# 02_Power.net
KiCad netlist of a schematic drawn in Altium Designer
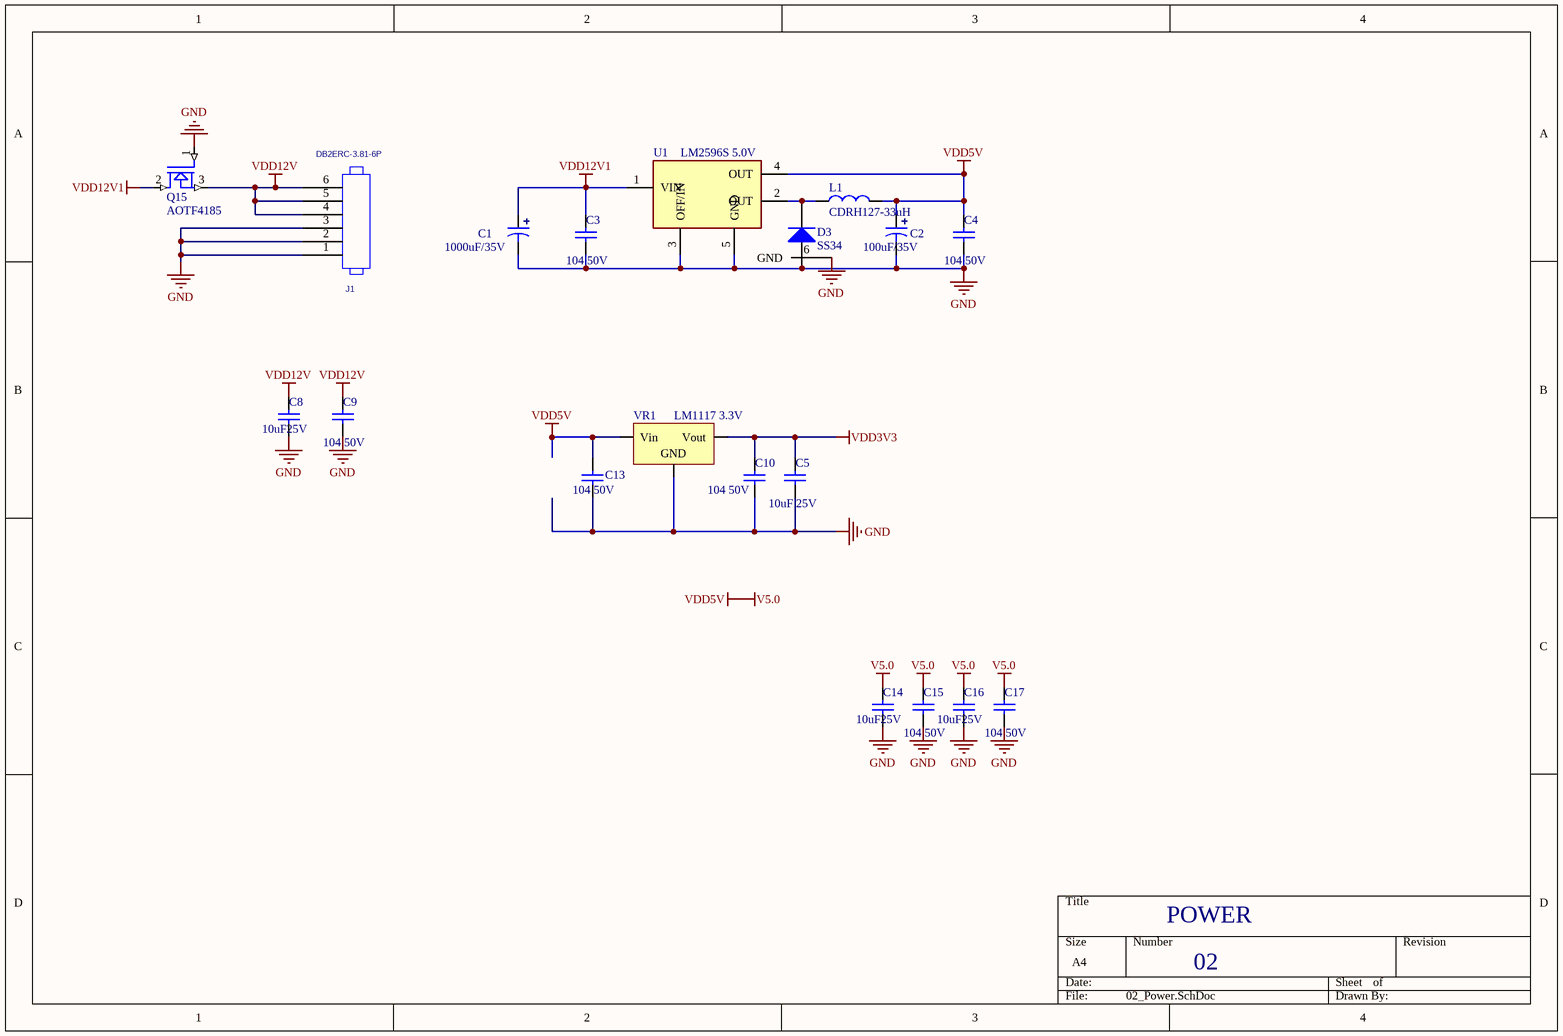
[diagram p0: 02_Power.SchDoc]

(export (version "E")
  (design (tool "Eeschema 10.0.6"))
  (components
    (comp (ref "C1")
      (value "1000uF/35V")
      (footprint "10*16")
      (description "电解电容")
      (libsource (lib "XiaoyI") (part "CAP2"))
    )
    (comp (ref "C2")
      (value "100uF/35V")
      (footprint "6*8")
      (description "电解电容")
      (libsource (lib "XiaoyI") (part "CAP2"))
    )
    (comp (ref "C3")
      (value "104 50V")
      (footprint "SMD-0805C")
      (description "贴片电容 10%")
      (libsource (lib "XiaoyI") (part "CAP4"))
    )
    (comp (ref "C4")
      (value "104 50V")
      (footprint "SMD-0805C")
      (description "贴片电容 10%")
      (libsource (lib "XiaoyI") (part "CAP4"))
    )
    (comp (ref "C5")
      (value "10uF 25V")
      (footprint "SMD-0603C")
      (description "贴片电容 20%")
      (libsource (lib "XiaoyI") (part "CAP4"))
    )
    (comp (ref "C8")
      (value "10uF25V")
      (footprint "SMD-0603C")
      (description "贴片电容 10%")
      (libsource (lib "XiaoyI") (part "CAP4"))
    )
    (comp (ref "C9")
      (value "104 50V")
      (footprint "SMD-0603C")
      (description "贴片电容 10%")
      (libsource (lib "XiaoyI") (part "CAP4"))
    )
    (comp (ref "C10")
      (value "104 50V")
      (footprint "SMD-0603C")
      (description "贴片电容 10%")
      (libsource (lib "XiaoyI") (part "CAP4"))
    )
    (comp (ref "C13")
      (value "104 50V")
      (footprint "SMD-0603C")
      (description "贴片电容 10%")
      (libsource (lib "XiaoyI") (part "CAP4"))
    )
    (comp (ref "C14")
      (value "10uF25V")
      (footprint "SMD-0603C")
      (description "贴片电容 20%")
      (libsource (lib "XiaoyI") (part "CAP4"))
    )
    (comp (ref "C15")
      (value "104 50V")
      (footprint "SMD-0603C")
      (description "贴片电容 20%")
      (libsource (lib "XiaoyI") (part "CAP4"))
    )
    (comp (ref "C16")
      (value "10uF25V")
      (footprint "SMD-0603C")
      (description "贴片电容 20%")
      (libsource (lib "XiaoyI") (part "CAP4"))
    )
    (comp (ref "C17")
      (value "104 50V")
      (footprint "SMD-0603C")
      (description "贴片电容 20%")
      (libsource (lib "XiaoyI") (part "CAP4"))
    )
    (comp (ref "D3") (value "SS34") (footprint "SMA") (libsource (lib "Sch_library") (part "DIODE")))
    (comp (ref "J1")
      (value "DB2ERC-3.81-6P")
      (footprint "VH-AW-3.96*6P")
      (fields (field (name "Comment") "HEADER_6"))
      (libsource (lib "liujingtao_V1.0") (part "HEADER_6"))
    )
    (comp (ref "L1")
      (value "CDRH127-33uH")
      (footprint "CDRH-127")
      (libsource (lib "Sch_library") (part "IND"))
    )
    (comp (ref "Q15")
      (value "AOTF4185")
      (footprint "to220")
      (description "MOSFET N")
      (libsource (lib "XiaoyI") (part "MOSFET N"))
    )
    (comp (ref "U1")
      (value "LM2596S 5.0V")
      (footprint "TO-263-5")
      (libsource (lib "Sch_library") (part "LM2596"))
    )
    (comp (ref "VR1")
      (value "LM1117 3.3V")
      (footprint "SOT223")
      (description "三端稳压器")
      (libsource (lib "XiaoyI") (part "LM1117"))
    )
  )
  (nets
    (net (code "1") (name "GND") (class "Default")
      (node (ref "C1") (pin "2") (pinfunction "2_2") (pintype "passive"))
      (node (ref "C10") (pin "1") (pinfunction "1_1") (pintype "passive"))
      (node (ref "C13") (pin "1") (pinfunction "1_1") (pintype "passive"))
      (node (ref "C14") (pin "1") (pinfunction "1_1") (pintype "passive"))
      (node (ref "C15") (pin "1") (pinfunction "1_1") (pintype "passive"))
      (node (ref "C16") (pin "1") (pinfunction "1_1") (pintype "passive"))
      (node (ref "C17") (pin "1") (pinfunction "1_1") (pintype "passive"))
      (node (ref "C2") (pin "2") (pinfunction "2_2") (pintype "passive"))
      (node (ref "C3") (pin "1") (pinfunction "1_1") (pintype "passive"))
      (node (ref "C4") (pin "1") (pinfunction "1_1") (pintype "passive"))
      (node (ref "C5") (pin "1") (pinfunction "1_1") (pintype "passive"))
      (node (ref "C8") (pin "1") (pinfunction "1_1") (pintype "passive"))
      (node (ref "C9") (pin "1") (pinfunction "1_1") (pintype "passive"))
      (node (ref "D3") (pin "1") (pinfunction "A_1") (pintype "passive"))
      (node (ref "J1") (pin "1") (pinfunction "1_1") (pintype "passive"))
      (node (ref "J1") (pin "2") (pinfunction "2_2") (pintype "passive"))
      (node (ref "J1") (pin "3") (pinfunction "3_3") (pintype "passive"))
      (node (ref "Q15") (pin "1") (pinfunction "G_1") (pintype "input"))
      (node (ref "U1") (pin "3") (pinfunction "OFF/IN_3") (pintype "passive"))
      (node (ref "U1") (pin "5") (pinfunction "GND_5") (pintype "passive"))
      (node (ref "U1") (pin "6") (pinfunction "GND_6") (pintype "passive"))
      (node (ref "VR1") (pin "1") (pinfunction "GND_1") (pintype "passive"))
    )
    (net (code "2") (name "Net-(D3-K)") (class "Default")
      (node (ref "D3") (pin "2") (pinfunction "K_2") (pintype "passive"))
      (node (ref "L1") (pin "1") (pinfunction "1_1") (pintype "passive"))
      (node (ref "U1") (pin "2") (pinfunction "OUT_2") (pintype "passive"))
    )
    (net (code "3") (name "V5.0") (class "Default")
      (node (ref "C13") (pin "2") (pinfunction "2_2") (pintype "passive"))
      (node (ref "C14") (pin "2") (pinfunction "2_2") (pintype "passive"))
      (node (ref "C15") (pin "2") (pinfunction "2_2") (pintype "passive"))
      (node (ref "C16") (pin "2") (pinfunction "2_2") (pintype "passive"))
      (node (ref "C17") (pin "2") (pinfunction "2_2") (pintype "passive"))
      (node (ref "C2") (pin "1") (pinfunction "1_1") (pintype "passive"))
      (node (ref "C4") (pin "2") (pinfunction "2_2") (pintype "passive"))
      (node (ref "L1") (pin "2") (pinfunction "2_2") (pintype "passive"))
      (node (ref "U1") (pin "4") (pinfunction "OUT_4") (pintype "passive"))
      (node (ref "VR1") (pin "3") (pinfunction "Vin_3") (pintype "passive"))
    )
    (net (code "4") (name "VDD3V3") (class "Default")
      (node (ref "C10") (pin "2") (pinfunction "2_2") (pintype "passive"))
      (node (ref "C5") (pin "2") (pinfunction "2_2") (pintype "passive"))
      (node (ref "VR1") (pin "2") (pinfunction "Vout_2") (pintype "passive"))
    )
    (net (code "5") (name "VDD12V") (class "Default")
      (node (ref "C8") (pin "2") (pinfunction "2_2") (pintype "passive"))
      (node (ref "C9") (pin "2") (pinfunction "2_2") (pintype "passive"))
      (node (ref "J1") (pin "4") (pinfunction "4_4") (pintype "passive"))
      (node (ref "J1") (pin "5") (pinfunction "5_5") (pintype "passive"))
      (node (ref "J1") (pin "6") (pinfunction "6_6") (pintype "passive"))
      (node (ref "Q15") (pin "3") (pinfunction "S_3") (pintype "output"))
    )
    (net (code "6") (name "VDD12V1") (class "Default")
      (node (ref "C1") (pin "1") (pinfunction "1_1") (pintype "passive"))
      (node (ref "C3") (pin "2") (pinfunction "2_2") (pintype "passive"))
      (node (ref "Q15") (pin "2") (pinfunction "D_2") (pintype "input"))
      (node (ref "U1") (pin "1") (pinfunction "VIN_1") (pintype "passive"))
    )
  )
)
